# indicator.net
KiCad netlist of a schematic drawn in Altium Designer
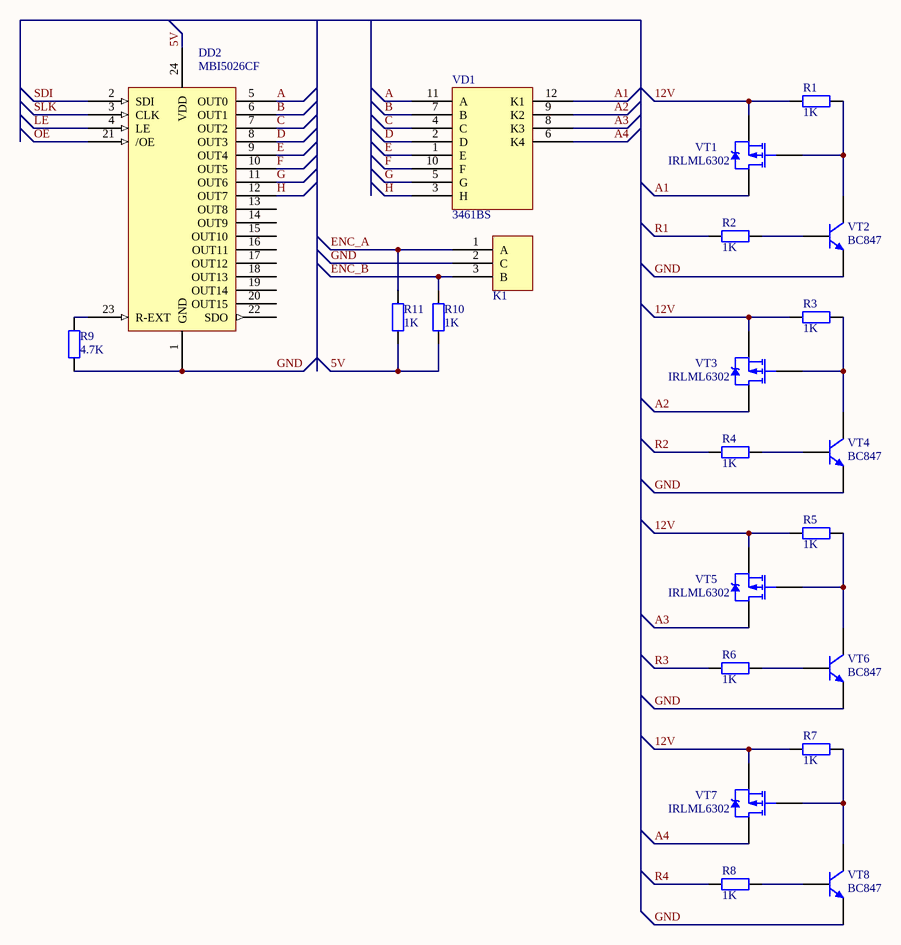
[diagram p0: indicator.SchDoc]

(export (version "E")
  (design (tool "Eeschema 10.0.6"))
  (components
    (comp (ref "DD2") (value "MBI5026CF") (footprint "SOP24") (libsource (lib "Schlib1") (part "MBI5026CF")))
    (comp (ref "K1")
      (value "EC12")
      (footprint "EC12E1220406")
      (libsource (lib "Schlib1") (part "EC12E1220406"))
    )
    (comp (ref "R1") (value "1K") (footprint "PcbLib1:R1206") (libsource (lib "") (part "Res_1")))
    (comp (ref "R2") (value "1K") (footprint "PcbLib1:R1206") (libsource (lib "") (part "Res_1")))
    (comp (ref "R3") (value "1K") (footprint "PcbLib1:R1206") (libsource (lib "") (part "Res_1")))
    (comp (ref "R4") (value "1K") (footprint "PcbLib1:R1206") (libsource (lib "") (part "Res_1")))
    (comp (ref "R5") (value "1K") (footprint "PcbLib1:R1206") (libsource (lib "") (part "Res_1")))
    (comp (ref "R6") (value "1K") (footprint "PcbLib1:R1206") (libsource (lib "") (part "Res_1")))
    (comp (ref "R7") (value "1K") (footprint "PcbLib1:R1206") (libsource (lib "") (part "Res_1")))
    (comp (ref "R8") (value "1K") (footprint "PcbLib1:R1206") (libsource (lib "") (part "Res_1")))
    (comp (ref "R9") (value "4.7K") (footprint "PcbLib1:R1206") (libsource (lib "Schlib1") (part "Res")))
    (comp (ref "R10") (value "1K") (footprint "PcbLib1:R1206") (libsource (lib "Schlib1") (part "Res")))
    (comp (ref "R11") (value "1K") (footprint "PcbLib1:R1206") (libsource (lib "Schlib1") (part "Res")))
    (comp (ref "VD1") (value "3461BS") (footprint "3461bs") (libsource (lib "Schlib1") (part "3461BS")))
    (comp (ref "VT1")
      (value "IRLML6302")
      (footprint "SOT-23_N")
      (description "HEXFET Power MOSFET")
      (fields (field (name "PUBLISHER") "Altium Limited"))
      (libsource (lib "IR Discrete MOSFET - Power") (part "IRLML6302"))
    )
    (comp (ref "VT2")
      (value "BC847")
      (footprint "SOT23_N")
      (description "NPN General-purpose Transistor")
      (fields (field (name "PUBLISHER") "Altium Limited"))
      (libsource (lib "Philips Discrete BJT - Low Power") (part "BC847"))
    )
    (comp (ref "VT3")
      (value "IRLML6302")
      (footprint "SOT-23_N")
      (description "HEXFET Power MOSFET")
      (fields (field (name "PUBLISHER") "Altium Limited"))
      (libsource (lib "IR Discrete MOSFET - Power") (part "IRLML6302"))
    )
    (comp (ref "VT4")
      (value "BC847")
      (footprint "SOT23_N")
      (description "NPN General-purpose Transistor")
      (fields (field (name "PUBLISHER") "Altium Limited"))
      (libsource (lib "Philips Discrete BJT - Low Power") (part "BC847"))
    )
    (comp (ref "VT5")
      (value "IRLML6302")
      (footprint "SOT-23_N")
      (description "HEXFET Power MOSFET")
      (fields (field (name "PUBLISHER") "Altium Limited"))
      (libsource (lib "IR Discrete MOSFET - Power") (part "IRLML6302"))
    )
    (comp (ref "VT6")
      (value "BC847")
      (footprint "SOT23_N")
      (description "NPN General-purpose Transistor")
      (fields (field (name "PUBLISHER") "Altium Limited"))
      (libsource (lib "Philips Discrete BJT - Low Power") (part "BC847"))
    )
    (comp (ref "VT7")
      (value "IRLML6302")
      (footprint "SOT-23_N")
      (description "HEXFET Power MOSFET")
      (fields (field (name "PUBLISHER") "Altium Limited"))
      (libsource (lib "IR Discrete MOSFET - Power") (part "IRLML6302"))
    )
    (comp (ref "VT8")
      (value "BC847")
      (footprint "SOT23_N")
      (description "NPN General-purpose Transistor")
      (fields (field (name "PUBLISHER") "Altium Limited"))
      (libsource (lib "Philips Discrete BJT - Low Power") (part "BC847"))
    )
  )
  (nets
    (net (code "1") (name "/5V") (class "Default")
      (node (ref "DD2") (pin "24") (pinfunction "VDD_24") (pintype "power_in"))
      (node (ref "R10") (pin "1") (pinfunction "1_1") (pintype "passive"))
      (node (ref "R11") (pin "1") (pinfunction "1_1") (pintype "passive"))
    )
    (net (code "2") (name "/12V") (class "Default")
      (node (ref "R1") (pin "2") (pinfunction "2_2") (pintype "passive"))
      (node (ref "R3") (pin "2") (pinfunction "2_2") (pintype "passive"))
      (node (ref "R5") (pin "2") (pinfunction "2_2") (pintype "passive"))
      (node (ref "R7") (pin "2") (pinfunction "2_2") (pintype "passive"))
      (node (ref "VT1") (pin "2") (pinfunction "S_2") (pintype "passive"))
      (node (ref "VT3") (pin "2") (pinfunction "S_2") (pintype "passive"))
      (node (ref "VT5") (pin "2") (pinfunction "S_2") (pintype "passive"))
      (node (ref "VT7") (pin "2") (pinfunction "S_2") (pintype "passive"))
    )
    (net (code "3") (name "/A") (class "Default")
      (node (ref "DD2") (pin "5") (pinfunction "OUT0_5") (pintype "open_collector"))
      (node (ref "VD1") (pin "11") (pinfunction "A_11") (pintype "passive"))
    )
    (net (code "4") (name "/A1") (class "Default")
      (node (ref "VD1") (pin "12") (pinfunction "K1_12") (pintype "passive"))
      (node (ref "VT1") (pin "3") (pinfunction "D_3") (pintype "passive"))
    )
    (net (code "5") (name "/A2") (class "Default")
      (node (ref "VD1") (pin "9") (pinfunction "K2_9") (pintype "passive"))
      (node (ref "VT3") (pin "3") (pinfunction "D_3") (pintype "passive"))
    )
    (net (code "6") (name "/A3") (class "Default")
      (node (ref "VD1") (pin "8") (pinfunction "K3_8") (pintype "passive"))
      (node (ref "VT5") (pin "3") (pinfunction "D_3") (pintype "passive"))
    )
    (net (code "7") (name "/A4") (class "Default")
      (node (ref "VD1") (pin "6") (pinfunction "K4_6") (pintype "passive"))
      (node (ref "VT7") (pin "3") (pinfunction "D_3") (pintype "passive"))
    )
    (net (code "8") (name "/B") (class "Default")
      (node (ref "DD2") (pin "6") (pinfunction "OUT1_6") (pintype "open_collector"))
      (node (ref "VD1") (pin "7") (pinfunction "B_7") (pintype "passive"))
    )
    (net (code "9") (name "/C") (class "Default")
      (node (ref "DD2") (pin "7") (pinfunction "OUT2_7") (pintype "open_collector"))
      (node (ref "VD1") (pin "4") (pinfunction "C_4") (pintype "passive"))
    )
    (net (code "10") (name "/D") (class "Default")
      (node (ref "DD2") (pin "8") (pinfunction "OUT3_8") (pintype "open_collector"))
      (node (ref "VD1") (pin "2") (pinfunction "D_2") (pintype "passive"))
    )
    (net (code "11") (name "/E") (class "Default")
      (node (ref "DD2") (pin "9") (pinfunction "OUT4_9") (pintype "open_collector"))
      (node (ref "VD1") (pin "1") (pinfunction "E_1") (pintype "passive"))
    )
    (net (code "12") (name "/ENC_A") (class "Default")
      (node (ref "K1") (pin "1") (pinfunction "A_1") (pintype "passive"))
      (node (ref "R11") (pin "2") (pinfunction "2_2") (pintype "passive"))
    )
    (net (code "13") (name "/ENC_B") (class "Default")
      (node (ref "K1") (pin "3") (pinfunction "B_3") (pintype "passive"))
      (node (ref "R10") (pin "2") (pinfunction "2_2") (pintype "passive"))
    )
    (net (code "14") (name "/F") (class "Default")
      (node (ref "DD2") (pin "10") (pinfunction "OUT5_10") (pintype "open_collector"))
      (node (ref "VD1") (pin "10") (pinfunction "F_10") (pintype "passive"))
    )
    (net (code "15") (name "/G") (class "Default")
      (node (ref "DD2") (pin "11") (pinfunction "OUT6_11") (pintype "open_collector"))
      (node (ref "VD1") (pin "5") (pinfunction "G_5") (pintype "passive"))
    )
    (net (code "16") (name "/GND") (class "Default")
      (node (ref "DD2") (pin "1") (pinfunction "GND_1") (pintype "power_in"))
      (node (ref "K1") (pin "2") (pinfunction "C_2") (pintype "passive"))
      (node (ref "R9") (pin "1") (pinfunction "1_1") (pintype "passive"))
      (node (ref "VT2") (pin "2") (pinfunction "E_2") (pintype "passive"))
      (node (ref "VT4") (pin "2") (pinfunction "E_2") (pintype "passive"))
      (node (ref "VT6") (pin "2") (pinfunction "E_2") (pintype "passive"))
      (node (ref "VT8") (pin "2") (pinfunction "E_2") (pintype "passive"))
    )
    (net (code "17") (name "/H") (class "Default")
      (node (ref "DD2") (pin "12") (pinfunction "OUT7_12") (pintype "open_collector"))
      (node (ref "VD1") (pin "3") (pinfunction "H_3") (pintype "passive"))
    )
    (net (code "18") (name "/LE") (class "Default")
      (node (ref "DD2") (pin "4") (pinfunction "LE_4") (pintype "input"))
    )
    (net (code "19") (name "/OE") (class "Default")
      (node (ref "DD2") (pin "21") (pinfunction "/OE_21") (pintype "input"))
    )
    (net (code "20") (name "/R1") (class "Default")
      (node (ref "R2") (pin "2") (pinfunction "2_2") (pintype "passive"))
    )
    (net (code "21") (name "/R2") (class "Default")
      (node (ref "R4") (pin "2") (pinfunction "2_2") (pintype "passive"))
    )
    (net (code "22") (name "/R3") (class "Default")
      (node (ref "R6") (pin "2") (pinfunction "2_2") (pintype "passive"))
    )
    (net (code "23") (name "/R4") (class "Default")
      (node (ref "R8") (pin "2") (pinfunction "2_2") (pintype "passive"))
    )
    (net (code "24") (name "/SDI") (class "Default")
      (node (ref "DD2") (pin "2") (pinfunction "SDI_2") (pintype "input"))
    )
    (net (code "25") (name "/SLK") (class "Default")
      (node (ref "DD2") (pin "3") (pinfunction "CLK_3") (pintype "input"))
    )
    (net (code "26") (name "Net-(DD2-R-EXT)") (class "Default")
      (node (ref "DD2") (pin "23") (pinfunction "R-EXT_23") (pintype "input"))
      (node (ref "R9") (pin "2") (pinfunction "2_2") (pintype "passive"))
    )
    (net (code "27") (name "Net-(VT1-G)") (class "Default")
      (node (ref "R1") (pin "1") (pinfunction "1_1") (pintype "passive"))
      (node (ref "VT1") (pin "1") (pinfunction "G_1") (pintype "passive"))
      (node (ref "VT2") (pin "3") (pinfunction "C_3") (pintype "passive"))
    )
    (net (code "28") (name "Net-(VT2-B)") (class "Default")
      (node (ref "R2") (pin "1") (pinfunction "1_1") (pintype "passive"))
      (node (ref "VT2") (pin "1") (pinfunction "B_1") (pintype "passive"))
    )
    (net (code "29") (name "Net-(VT3-G)") (class "Default")
      (node (ref "R3") (pin "1") (pinfunction "1_1") (pintype "passive"))
      (node (ref "VT3") (pin "1") (pinfunction "G_1") (pintype "passive"))
      (node (ref "VT4") (pin "3") (pinfunction "C_3") (pintype "passive"))
    )
    (net (code "30") (name "Net-(VT4-B)") (class "Default")
      (node (ref "R4") (pin "1") (pinfunction "1_1") (pintype "passive"))
      (node (ref "VT4") (pin "1") (pinfunction "B_1") (pintype "passive"))
    )
    (net (code "31") (name "Net-(VT5-G)") (class "Default")
      (node (ref "R5") (pin "1") (pinfunction "1_1") (pintype "passive"))
      (node (ref "VT5") (pin "1") (pinfunction "G_1") (pintype "passive"))
      (node (ref "VT6") (pin "3") (pinfunction "C_3") (pintype "passive"))
    )
    (net (code "32") (name "Net-(VT6-B)") (class "Default")
      (node (ref "R6") (pin "1") (pinfunction "1_1") (pintype "passive"))
      (node (ref "VT6") (pin "1") (pinfunction "B_1") (pintype "passive"))
    )
    (net (code "33") (name "Net-(VT7-G)") (class "Default")
      (node (ref "R7") (pin "1") (pinfunction "1_1") (pintype "passive"))
      (node (ref "VT7") (pin "1") (pinfunction "G_1") (pintype "passive"))
      (node (ref "VT8") (pin "3") (pinfunction "C_3") (pintype "passive"))
    )
    (net (code "34") (name "Net-(VT8-B)") (class "Default")
      (node (ref "R8") (pin "1") (pinfunction "1_1") (pintype "passive"))
      (node (ref "VT8") (pin "1") (pinfunction "B_1") (pintype "passive"))
    )
    (net (code "35") (name "unconnected-(DD2-OUT8-Pad13)") (class "Default")
      (node (ref "DD2") (pin "13") (pinfunction "OUT8_13") (pintype "open_collector"))
    )
    (net (code "36") (name "unconnected-(DD2-OUT9-Pad14)") (class "Default")
      (node (ref "DD2") (pin "14") (pinfunction "OUT9_14") (pintype "open_collector"))
    )
    (net (code "37") (name "unconnected-(DD2-OUT10-Pad15)") (class "Default")
      (node (ref "DD2") (pin "15") (pinfunction "OUT10_15") (pintype "open_collector"))
    )
    (net (code "38") (name "unconnected-(DD2-OUT11-Pad16)") (class "Default")
      (node (ref "DD2") (pin "16") (pinfunction "OUT11_16") (pintype "open_collector"))
    )
    (net (code "39") (name "unconnected-(DD2-OUT12-Pad17)") (class "Default")
      (node (ref "DD2") (pin "17") (pinfunction "OUT12_17") (pintype "open_collector"))
    )
    (net (code "40") (name "unconnected-(DD2-OUT13-Pad18)") (class "Default")
      (node (ref "DD2") (pin "18") (pinfunction "OUT13_18") (pintype "open_collector"))
    )
    (net (code "41") (name "unconnected-(DD2-OUT14-Pad19)") (class "Default")
      (node (ref "DD2") (pin "19") (pinfunction "OUT14_19") (pintype "open_collector"))
    )
    (net (code "42") (name "unconnected-(DD2-OUT15-Pad20)") (class "Default")
      (node (ref "DD2") (pin "20") (pinfunction "OUT15_20") (pintype "open_collector"))
    )
    (net (code "43") (name "unconnected-(DD2-SDO-Pad22)") (class "Default")
      (node (ref "DD2") (pin "22") (pinfunction "SDO_22") (pintype "output"))
    )
  )
)
